# tea_breakout.net
KiCad netlist of a schematic drawn in EAGLE
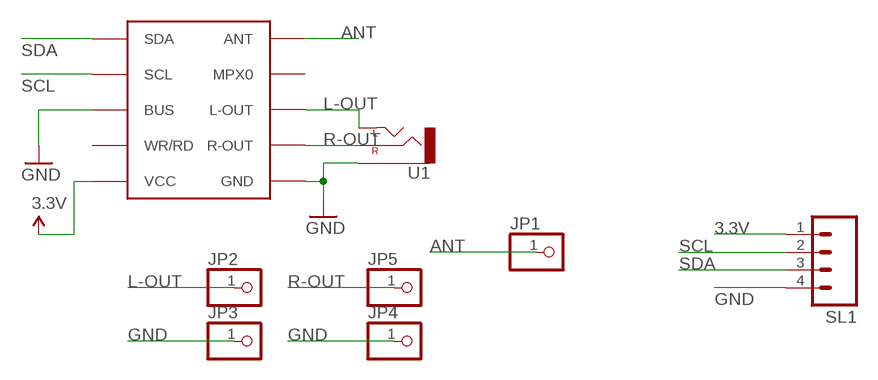
[diagram p0: schematic, sheet 1]

(export (version "E")
  (design (tool "Eeschema 10.0.6"))
  (components
    (comp (ref "JP1")
      (value "PINHD-1X1")
      (footprint "eagle-import:1X01")
      (libsource (lib "eagle-import") (part "PINHD-1X1"))
    )
    (comp (ref "JP2")
      (value "PINHD-1X1")
      (footprint "eagle-import:1X01")
      (libsource (lib "eagle-import") (part "PINHD-1X1"))
    )
    (comp (ref "JP3")
      (value "PINHD-1X1")
      (footprint "eagle-import:1X01")
      (libsource (lib "eagle-import") (part "PINHD-1X1"))
    )
    (comp (ref "JP4")
      (value "PINHD-1X1")
      (footprint "eagle-import:1X01")
      (libsource (lib "eagle-import") (part "PINHD-1X1"))
    )
    (comp (ref "JP5")
      (value "PINHD-1X1")
      (footprint "eagle-import:1X01")
      (libsource (lib "eagle-import") (part "PINHD-1X1"))
    )
    (comp (ref "SL1")
      (value "M041X04_NO_SILK")
      (footprint "eagle-import:1X04_NO_SILK")
      (libsource (lib "eagle-import") (part "M041X04_NO_SILK"))
    )
    (comp (ref "U$1")
      (value "PL102BC-N")
      (footprint "eagle-import:PL102BC-N")
      (libsource (lib "eagle-import") (part "PL102BC-N"))
    )
    (comp (ref "U1")
      (value "AUDIO-JACKPTH")
      (footprint "eagle-import:AUDIO-JACK")
      (libsource (lib "eagle-import") (part "AUDIO-JACKPTH"))
    )
  )
  (nets
    (net (code "1") (name "/ANT") (class "Default")
      (node (ref "JP1") (pin "1") (pinfunction "1_1") (pintype "passive"))
      (node (ref "U$1") (pin "PAD11") (pinfunction "ANT_PAD11") (pintype "bidirectional"))
    )
    (net (code "2") (name "/L-OUT") (class "Default")
      (node (ref "JP2") (pin "1") (pinfunction "1_1") (pintype "passive"))
      (node (ref "U$1") (pin "PAD9") (pinfunction "L-OUT_PAD9") (pintype "bidirectional"))
      (node (ref "U1") (pin "TIP") (pinfunction "LEFT_TIP") (pintype "bidirectional"))
    )
    (net (code "3") (name "/R-OUT") (class "Default")
      (node (ref "JP5") (pin "1") (pinfunction "1_1") (pintype "passive"))
      (node (ref "U$1") (pin "PAD7") (pinfunction "R-OUT_PAD7") (pintype "bidirectional"))
      (node (ref "U1") (pin "RING") (pinfunction "RIGHT_RING") (pintype "bidirectional"))
    )
    (net (code "4") (name "/SCL") (class "Default")
      (node (ref "SL1") (pin "2") (pinfunction "2_2") (pintype "passive"))
      (node (ref "U$1") (pin "PAD2") (pinfunction "SCL_PAD2") (pintype "bidirectional"))
    )
    (net (code "5") (name "/SDA") (class "Default")
      (node (ref "SL1") (pin "3") (pinfunction "3_3") (pintype "passive"))
      (node (ref "U$1") (pin "PAD1") (pinfunction "SDA_PAD1") (pintype "bidirectional"))
    )
    (net (code "6") (name "3.3V") (class "Default")
      (node (ref "SL1") (pin "1") (pinfunction "1_1") (pintype "passive"))
      (node (ref "U$1") (pin "PAD5") (pinfunction "VCC_PAD5") (pintype "bidirectional"))
    )
    (net (code "7") (name "GND") (class "Default")
      (node (ref "JP3") (pin "1") (pinfunction "1_1") (pintype "passive"))
      (node (ref "JP4") (pin "1") (pinfunction "1_1") (pintype "passive"))
      (node (ref "SL1") (pin "4") (pinfunction "4_4") (pintype "passive"))
      (node (ref "U$1") (pin "PAD3") (pinfunction "BUS_PAD3") (pintype "bidirectional"))
      (node (ref "U$1") (pin "PAD6") (pinfunction "GND_PAD6") (pintype "bidirectional"))
      (node (ref "U1") (pin "SLEEVE") (pinfunction "SLEEVE_SLEEVE") (pintype "bidirectional"))
    )
    (net (code "8") (name "unconnected-(U$1-MPX0-PadPAD10)") (class "Default")
      (node (ref "U$1") (pin "PAD10") (pinfunction "MPX0_PAD10") (pintype "bidirectional"))
    )
    (net (code "9") (name "unconnected-(U$1-WR{slash}RD-PadPAD4)") (class "Default")
      (node (ref "U$1") (pin "PAD4") (pinfunction "WR/RD_PAD4") (pintype "bidirectional"))
    )
  )
)
